# CONNECTOR.net
KiCad netlist of a schematic drawn in Altium Designer
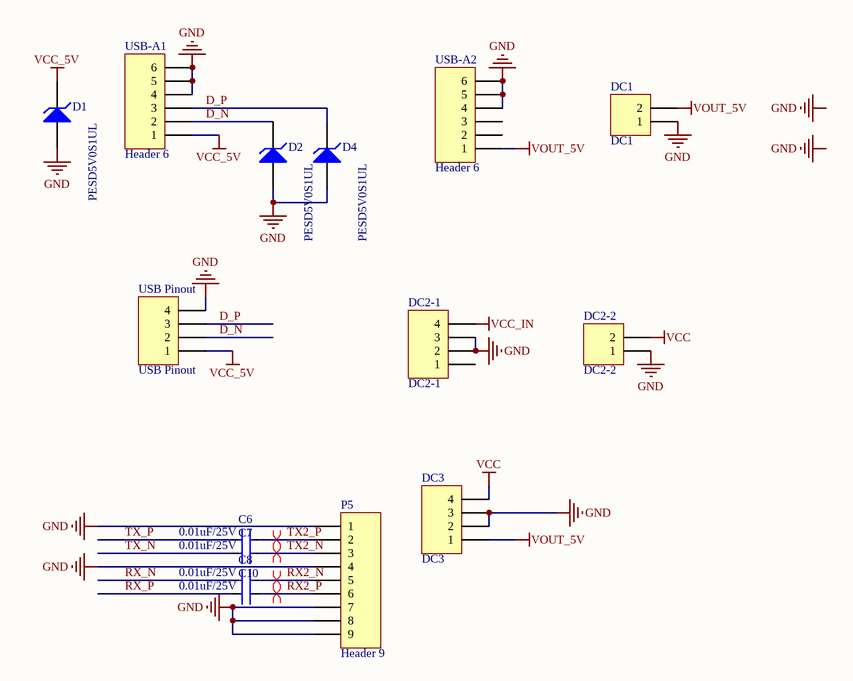
[diagram p0: CONNECTOR.SchDoc]

(export (version "E")
  (design (tool "Eeschema 10.0.6"))
  (components
    (comp (ref "C6")
      (value "0.01uF/25V")
      (footprint "0603C")
      (description "CCX85-103")
      (libsource (lib "无极性电容") (part "0.01UF"))
    )
    (comp (ref "C7")
      (value "0.01uF/25V")
      (footprint "0603C")
      (description "CCX85-103")
      (libsource (lib "无极性电容") (part "0.01UF"))
    )
    (comp (ref "C8")
      (value "0.01uF/25V")
      (footprint "0603C")
      (description "CCX85-103")
      (libsource (lib "无极性电容") (part "0.01UF"))
    )
    (comp (ref "C10")
      (value "0.01uF/25V")
      (footprint "0603C")
      (description "CCX85-103")
      (libsource (lib "无极性电容") (part "0.01UF"))
    )
    (comp (ref "D1")
      (value "PESD5V0S1UL")
      (footprint "0402R")
      (description "Zener Diode")
      (fields (field (name "PUBLISHER") "Altium Limited"))
      (libsource (lib "Miscellaneous Devices") (part "D Zener"))
    )
    (comp (ref "D2")
      (value "PESD5V0S1UL")
      (footprint "0402R")
      (description "Zener Diode")
      (fields (field (name "PUBLISHER") "Altium Limited"))
      (libsource (lib "Miscellaneous Devices") (part "D Zener"))
    )
    (comp (ref "D4")
      (value "PESD5V0S1UL")
      (footprint "0402R")
      (description "Zener Diode")
      (fields (field (name "PUBLISHER") "Altium Limited"))
      (libsource (lib "Miscellaneous Devices") (part "D Zener"))
    )
    (comp (ref "DC1")
      (value "DC1")
      (footprint "2X2MMZ")
      (description "Header, 2-Pin")
      (fields (field (name "PUBLISHER") "Altium Limited"))
      (libsource (lib "Miscellaneous Connectors") (part "Header 2"))
    )
    (comp (ref "DC2-1")
      (value "DC2-1")
      (footprint "DC005")
      (description "Header, 4-Pin")
      (fields (field (name "PUBLISHER") "Altium Limited"))
      (libsource (lib "Miscellaneous Connectors") (part "Header 4"))
    )
    (comp (ref "DC2-2")
      (value "DC2-2")
      (footprint "2X2MMZ")
      (description "Header, 2-Pin")
      (fields (field (name "PUBLISHER") "Altium Limited"))
      (libsource (lib "Miscellaneous Connectors") (part "Header 2"))
    )
    (comp (ref "DC3")
      (value "DC3")
      (footprint "2X4MMZ")
      (description "Header, 4-Pin")
      (fields (field (name "PUBLISHER") "Altium Limited"))
      (libsource (lib "Miscellaneous Connectors") (part "Header 4"))
    )
    (comp (ref "P5")
      (value "Header 9")
      (footprint "SATA 7P")
      (description "Header, 9-Pin")
      (fields (field (name "PUBLISHER") "Altium Limited"))
      (libsource (lib "Miscellaneous Connectors") (part "Header 9"))
    )
    (comp (ref "USB Pinout")
      (value "USB Pinout")
      (footprint "sip-4l")
      (description "Header, 4-Pin")
      (fields (field (name "PUBLISHER") "Altium Limited"))
      (libsource (lib "Miscellaneous Connectors") (part "Header 4"))
    )
    (comp (ref "USB-A1")
      (value "Header 6")
      (footprint "USB-A-C")
      (description "Header, 6-Pin")
      (fields (field (name "PUBLISHER") "Altium Limited"))
      (libsource (lib "Miscellaneous Connectors") (part "Header 6"))
    )
    (comp (ref "USB-A2")
      (value "Header 6")
      (footprint "USB-A-C")
      (description "Header, 6-Pin")
      (fields (field (name "PUBLISHER") "Altium Limited"))
      (libsource (lib "Miscellaneous Connectors") (part "Header 6"))
    )
  )
  (nets
    (net (code "1") (name "/D_N") (class "Default")
      (node (ref "D2") (pin "2") (pinfunction "K_2") (pintype "passive"))
      (node (ref "USB Pinout") (pin "2") (pinfunction "2_2") (pintype "passive"))
      (node (ref "USB-A1") (pin "2") (pinfunction "2_2") (pintype "passive"))
    )
    (net (code "2") (name "/D_P") (class "Default")
      (node (ref "D4") (pin "2") (pinfunction "K_2") (pintype "passive"))
      (node (ref "USB Pinout") (pin "3") (pinfunction "3_3") (pintype "passive"))
      (node (ref "USB-A1") (pin "3") (pinfunction "3_3") (pintype "passive"))
    )
    (net (code "3") (name "/RX2_N") (class "Default")
      (node (ref "C8") (pin "2") (pinfunction "2_2") (pintype "passive"))
      (node (ref "P5") (pin "5") (pinfunction "5_5") (pintype "passive"))
    )
    (net (code "4") (name "/RX2_P") (class "Default")
      (node (ref "C10") (pin "2") (pinfunction "2_2") (pintype "passive"))
      (node (ref "P5") (pin "6") (pinfunction "6_6") (pintype "passive"))
    )
    (net (code "5") (name "/RX_N") (class "Default")
      (node (ref "C8") (pin "1") (pinfunction "1_1") (pintype "passive"))
    )
    (net (code "6") (name "/RX_P") (class "Default")
      (node (ref "C10") (pin "1") (pinfunction "1_1") (pintype "passive"))
    )
    (net (code "7") (name "/TX2_N") (class "Default")
      (node (ref "C7") (pin "2") (pinfunction "2_2") (pintype "passive"))
      (node (ref "P5") (pin "3") (pinfunction "3_3") (pintype "passive"))
    )
    (net (code "8") (name "/TX2_P") (class "Default")
      (node (ref "C6") (pin "2") (pinfunction "2_2") (pintype "passive"))
      (node (ref "P5") (pin "2") (pinfunction "2_2") (pintype "passive"))
    )
    (net (code "9") (name "/TX_N") (class "Default")
      (node (ref "C7") (pin "1") (pinfunction "1_1") (pintype "passive"))
    )
    (net (code "10") (name "/TX_P") (class "Default")
      (node (ref "C6") (pin "1") (pinfunction "1_1") (pintype "passive"))
    )
    (net (code "11") (name "GND") (class "Default")
      (node (ref "D1") (pin "1") (pinfunction "A_1") (pintype "passive"))
      (node (ref "D2") (pin "1") (pinfunction "A_1") (pintype "passive"))
      (node (ref "D4") (pin "1") (pinfunction "A_1") (pintype "passive"))
      (node (ref "DC1") (pin "1") (pinfunction "1_1") (pintype "passive"))
      (node (ref "DC2-1") (pin "2") (pinfunction "2_2") (pintype "passive"))
      (node (ref "DC2-1") (pin "3") (pinfunction "3_3") (pintype "passive"))
      (node (ref "DC2-2") (pin "1") (pinfunction "1_1") (pintype "passive"))
      (node (ref "DC3") (pin "2") (pinfunction "2_2") (pintype "passive"))
      (node (ref "DC3") (pin "3") (pinfunction "3_3") (pintype "passive"))
      (node (ref "P5") (pin "1") (pinfunction "1_1") (pintype "passive"))
      (node (ref "P5") (pin "4") (pinfunction "4_4") (pintype "passive"))
      (node (ref "P5") (pin "7") (pinfunction "7_7") (pintype "passive"))
      (node (ref "P5") (pin "8") (pinfunction "8_8") (pintype "passive"))
      (node (ref "P5") (pin "9") (pinfunction "9_9") (pintype "passive"))
      (node (ref "USB Pinout") (pin "4") (pinfunction "4_4") (pintype "passive"))
      (node (ref "USB-A1") (pin "4") (pinfunction "4_4") (pintype "passive"))
      (node (ref "USB-A1") (pin "5") (pinfunction "5_5") (pintype "passive"))
      (node (ref "USB-A1") (pin "6") (pinfunction "6_6") (pintype "passive"))
      (node (ref "USB-A2") (pin "4") (pinfunction "4_4") (pintype "passive"))
      (node (ref "USB-A2") (pin "5") (pinfunction "5_5") (pintype "passive"))
      (node (ref "USB-A2") (pin "6") (pinfunction "6_6") (pintype "passive"))
    )
    (net (code "12") (name "VCC") (class "Default")
      (node (ref "DC2-2") (pin "2") (pinfunction "2_2") (pintype "passive"))
      (node (ref "DC3") (pin "4") (pinfunction "4_4") (pintype "passive"))
    )
    (net (code "13") (name "VCC_5V") (class "Default")
      (node (ref "D1") (pin "2") (pinfunction "K_2") (pintype "passive"))
      (node (ref "USB Pinout") (pin "1") (pinfunction "1_1") (pintype "passive"))
      (node (ref "USB-A1") (pin "1") (pinfunction "1_1") (pintype "passive"))
    )
    (net (code "14") (name "VCC_IN") (class "Default")
      (node (ref "DC2-1") (pin "4") (pinfunction "4_4") (pintype "passive"))
    )
    (net (code "15") (name "VOUT_5V") (class "Default")
      (node (ref "DC1") (pin "2") (pinfunction "2_2") (pintype "passive"))
      (node (ref "DC3") (pin "1") (pinfunction "1_1") (pintype "passive"))
      (node (ref "USB-A2") (pin "1") (pinfunction "1_1") (pintype "passive"))
    )
    (net (code "16") (name "unconnected-(DC2-1-Pad1)") (class "Default")
      (node (ref "DC2-1") (pin "1") (pinfunction "1_1") (pintype "passive"))
    )
    (net (code "17") (name "unconnected-(USB-A2-Pad2)") (class "Default")
      (node (ref "USB-A2") (pin "2") (pinfunction "2_2") (pintype "passive"))
    )
    (net (code "18") (name "unconnected-(USB-A2-Pad3)") (class "Default")
      (node (ref "USB-A2") (pin "3") (pinfunction "3_3") (pintype "passive"))
    )
  )
)
